# uDuino.net
KiCad netlist of a schematic drawn in EAGLE
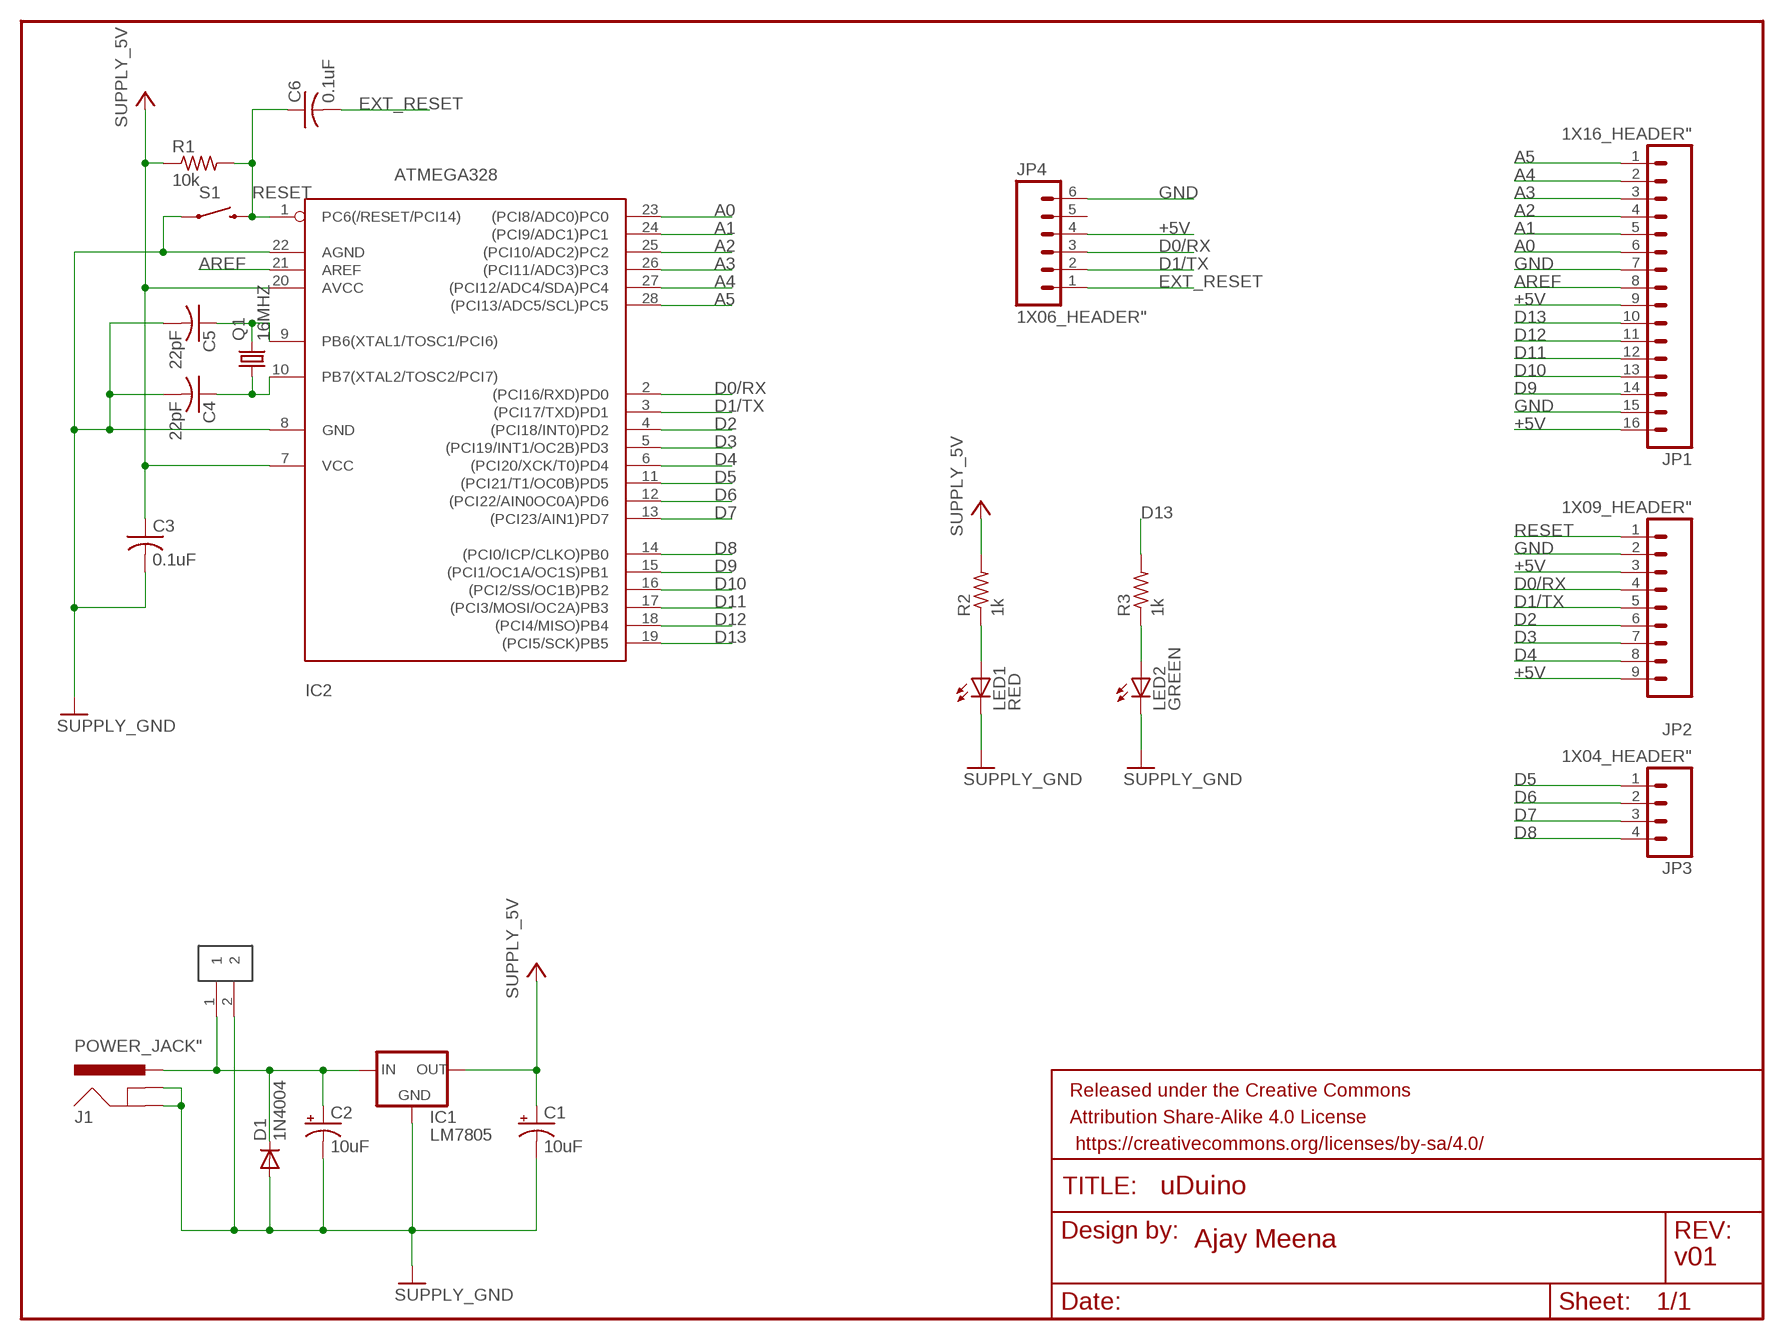
[diagram p0: schematic, sheet 1]

(export (version "E")
  (design (tool "Eeschema 10.0.6"))
  (components
    (comp (ref "C1")
      (value "10uF")
      (footprint "eagle-import:ELECTROLYTIC_CAP")
      (libsource (lib "eagle-import") (part "ELECTROLYTIC_CAP2.54MM"))
    )
    (comp (ref "C2")
      (value "10uF")
      (footprint "eagle-import:ELECTROLYTIC_CAP")
      (libsource (lib "eagle-import") (part "ELECTROLYTIC_CAP2.54MM"))
    )
    (comp (ref "C3")
      (value "0.1uF")
      (footprint "eagle-import:UNPOLARIZED_CAP")
      (libsource (lib "eagle-import") (part "UNPOLARIZED_CAP{dblquote}"))
    )
    (comp (ref "C4")
      (value "22pF")
      (footprint "eagle-import:UNPOLARIZED_CAP")
      (libsource (lib "eagle-import") (part "UNPOLARIZED_CAP{dblquote}"))
    )
    (comp (ref "C5")
      (value "22pF")
      (footprint "eagle-import:UNPOLARIZED_CAP")
      (libsource (lib "eagle-import") (part "UNPOLARIZED_CAP{dblquote}"))
    )
    (comp (ref "C6")
      (value "0.1uF")
      (footprint "eagle-import:UNPOLARIZED_CAP")
      (libsource (lib "eagle-import") (part "UNPOLARIZED_CAP{dblquote}"))
    )
    (comp (ref "D1")
      (value "1N4004")
      (footprint "eagle-import:DO41-10")
      (libsource (lib "eagle-import") (part "1N4004"))
    )
    (comp (ref "FRAME1")
      (value "FRAME-LETTERNO_PACKAGE")
      (footprint "eagle-import:DUMMY")
      (fields
        (field (name "DESIGNER") "Nobody")
        (field (name "VERSION") "v01")
        (field (name "DESIGNER_1") "Ajay Meena")
      )
      (libsource (lib "eagle-import") (part "FRAME-LETTERNO_PACKAGE"))
    )
    (comp (ref "IC1")
      (value "LM7805")
      (footprint "eagle-import:L4931_REGULATOR")
      (libsource (lib "eagle-import") (part "REGULATOR"))
    )
    (comp (ref "IC2")
      (value "ATMEGA328")
      (footprint "eagle-import:ATMEGA328")
      (libsource (lib "eagle-import") (part "ATMEGA328{dblquote}"))
    )
    (comp (ref "J1")
      (value "POWER_JACK\"")
      (footprint "eagle-import:POWER_JACK")
      (libsource (lib "eagle-import") (part "POWER_JACK{dblquote}"))
    )
    (comp (ref "JP1")
      (value "1X16_HEADER\"")
      (footprint "eagle-import:1X16_HEADER")
      (libsource (lib "eagle-import") (part "1X16_HEADER{dblquote}"))
    )
    (comp (ref "JP2")
      (value "1X09_HEADER\"")
      (footprint "eagle-import:1X09_HEADER")
      (libsource (lib "eagle-import") (part "1X09_HEADER{dblquote}"))
    )
    (comp (ref "JP3")
      (value "1X04_HEADER\"")
      (footprint "eagle-import:1X04_HEADER")
      (libsource (lib "eagle-import") (part "1X04_HEADER{dblquote}"))
    )
    (comp (ref "JP4")
      (value "1X06_HEADER\"")
      (footprint "eagle-import:1X06_HEADER")
      (libsource (lib "eagle-import") (part "1X06_HEADER{dblquote}"))
    )
    (comp (ref "JP5")
      (value "1X02_HEADER")
      (footprint "eagle-import:1X02_HEADER")
      (libsource (lib "eagle-import") (part "1X02_HEADER"))
    )
    (comp (ref "LED1")
      (value "RED")
      (footprint "eagle-import:LED5MM")
      (libsource (lib "eagle-import") (part "LED5MM"))
    )
    (comp (ref "LED2")
      (value "GREEN")
      (footprint "eagle-import:LED5MM")
      (libsource (lib "eagle-import") (part "LED5MM"))
    )
    (comp (ref "Q1")
      (value "16MHZ")
      (footprint "eagle-import:HC49_S")
      (libsource (lib "eagle-import") (part "CRYSTALHC49S"))
    )
    (comp (ref "R1")
      (value "10k")
      (footprint "eagle-import:0204_7")
      (libsource (lib "eagle-import") (part "R-US_0204/7"))
    )
    (comp (ref "R2")
      (value "1k")
      (footprint "eagle-import:0204_7")
      (libsource (lib "eagle-import") (part "R-US_0204/7"))
    )
    (comp (ref "R3")
      (value "1k")
      (footprint "eagle-import:0204_7")
      (libsource (lib "eagle-import") (part "R-US_0204/7"))
    )
    (comp (ref "S1")
      (value "MOMENTARY_SWITCH\"")
      (footprint "eagle-import:MOMENTARY_SWITCH")
      (libsource (lib "eagle-import") (part "MOMENTARY_SWITCH{dblquote}"))
    )
  )
  (nets
    (net (code "1") (name "/A0") (class "Default")
      (node (ref "IC2") (pin "23") (pinfunction "(PCI8/ADC0)PC0_23") (pintype "bidirectional"))
      (node (ref "JP1") (pin "6") (pinfunction "6_6") (pintype "passive"))
    )
    (net (code "2") (name "/A1") (class "Default")
      (node (ref "IC2") (pin "24") (pinfunction "(PCI9/ADC1)PC1_24") (pintype "bidirectional"))
      (node (ref "JP1") (pin "5") (pinfunction "5_5") (pintype "passive"))
    )
    (net (code "3") (name "/A2") (class "Default")
      (node (ref "IC2") (pin "25") (pinfunction "(PCI10/ADC2)PC2_25") (pintype "bidirectional"))
      (node (ref "JP1") (pin "4") (pinfunction "4_4") (pintype "passive"))
    )
    (net (code "4") (name "/A3") (class "Default")
      (node (ref "IC2") (pin "26") (pinfunction "(PCI11/ADC3)PC3_26") (pintype "bidirectional"))
      (node (ref "JP1") (pin "3") (pinfunction "3_3") (pintype "passive"))
    )
    (net (code "5") (name "/A4") (class "Default")
      (node (ref "IC2") (pin "27") (pinfunction "(PCI12/ADC4/SDA)PC4_27") (pintype "bidirectional"))
      (node (ref "JP1") (pin "2") (pinfunction "2_2") (pintype "passive"))
    )
    (net (code "6") (name "/A5") (class "Default")
      (node (ref "IC2") (pin "28") (pinfunction "(PCI13/ADC5/SCL)PC5_28") (pintype "bidirectional"))
      (node (ref "JP1") (pin "1") (pinfunction "1_1") (pintype "passive"))
    )
    (net (code "7") (name "/AREF") (class "Default")
      (node (ref "IC2") (pin "21") (pinfunction "AREF_21") (pintype "bidirectional"))
      (node (ref "JP1") (pin "8") (pinfunction "8_8") (pintype "passive"))
    )
    (net (code "8") (name "/D0{slash}RX") (class "Default")
      (node (ref "IC2") (pin "2") (pinfunction "(PCI16/RXD)PD0_2") (pintype "bidirectional"))
      (node (ref "JP2") (pin "4") (pinfunction "4_4") (pintype "passive"))
      (node (ref "JP4") (pin "3") (pinfunction "3_3") (pintype "passive"))
    )
    (net (code "9") (name "/D1{slash}TX") (class "Default")
      (node (ref "IC2") (pin "3") (pinfunction "(PCI17/TXD)PD1_3") (pintype "bidirectional"))
      (node (ref "JP2") (pin "5") (pinfunction "5_5") (pintype "passive"))
      (node (ref "JP4") (pin "2") (pinfunction "2_2") (pintype "passive"))
    )
    (net (code "10") (name "/D2") (class "Default")
      (node (ref "IC2") (pin "4") (pinfunction "(PCI18/INT0)PD2_4") (pintype "bidirectional"))
      (node (ref "JP2") (pin "6") (pinfunction "6_6") (pintype "passive"))
    )
    (net (code "11") (name "/D3") (class "Default")
      (node (ref "IC2") (pin "5") (pinfunction "(PCI19/INT1/OC2B)PD3_5") (pintype "bidirectional"))
      (node (ref "JP2") (pin "7") (pinfunction "7_7") (pintype "passive"))
    )
    (net (code "12") (name "/D4") (class "Default")
      (node (ref "IC2") (pin "6") (pinfunction "(PCI20/XCK/T0)PD4_6") (pintype "bidirectional"))
      (node (ref "JP2") (pin "8") (pinfunction "8_8") (pintype "passive"))
    )
    (net (code "13") (name "/D5") (class "Default")
      (node (ref "IC2") (pin "11") (pinfunction "(PCI21/T1/OC0B)PD5_11") (pintype "bidirectional"))
      (node (ref "JP3") (pin "1") (pinfunction "1_1") (pintype "passive"))
    )
    (net (code "14") (name "/D6") (class "Default")
      (node (ref "IC2") (pin "12") (pinfunction "(PCI22/AIN0OC0A)PD6_12") (pintype "bidirectional"))
      (node (ref "JP3") (pin "2") (pinfunction "2_2") (pintype "passive"))
    )
    (net (code "15") (name "/D7") (class "Default")
      (node (ref "IC2") (pin "13") (pinfunction "(PCI23/AIN1)PD7_13") (pintype "bidirectional"))
      (node (ref "JP3") (pin "3") (pinfunction "3_3") (pintype "passive"))
    )
    (net (code "16") (name "/D8") (class "Default")
      (node (ref "IC2") (pin "14") (pinfunction "(PCI0/ICP/CLKO)PB0_14") (pintype "bidirectional"))
      (node (ref "JP3") (pin "4") (pinfunction "4_4") (pintype "passive"))
    )
    (net (code "17") (name "/D9") (class "Default")
      (node (ref "IC2") (pin "15") (pinfunction "(PCI1/OC1A/OC1S)PB1_15") (pintype "bidirectional"))
      (node (ref "JP1") (pin "14") (pinfunction "14_14") (pintype "passive"))
    )
    (net (code "18") (name "/D10") (class "Default")
      (node (ref "IC2") (pin "16") (pinfunction "(PCI2/SS/OC1B)PB2_16") (pintype "bidirectional"))
      (node (ref "JP1") (pin "13") (pinfunction "13_13") (pintype "passive"))
    )
    (net (code "19") (name "/D11") (class "Default")
      (node (ref "IC2") (pin "17") (pinfunction "(PCI3/MOSI/OC2A)PB3_17") (pintype "bidirectional"))
      (node (ref "JP1") (pin "12") (pinfunction "12_12") (pintype "passive"))
    )
    (net (code "20") (name "/D12") (class "Default")
      (node (ref "IC2") (pin "18") (pinfunction "(PCI4/MISO)PB4_18") (pintype "bidirectional"))
      (node (ref "JP1") (pin "11") (pinfunction "11_11") (pintype "passive"))
    )
    (net (code "21") (name "/D13") (class "Default")
      (node (ref "IC2") (pin "19") (pinfunction "(PCI5/SCK)PB5_19") (pintype "bidirectional"))
      (node (ref "JP1") (pin "10") (pinfunction "10_10") (pintype "passive"))
      (node (ref "R3") (pin "2") (pinfunction "2_2") (pintype "passive"))
    )
    (net (code "22") (name "/EXT_RESET") (class "Default")
      (node (ref "C6") (pin "2") (pinfunction "2_2") (pintype "passive"))
      (node (ref "JP4") (pin "1") (pinfunction "1_1") (pintype "passive"))
    )
    (net (code "23") (name "/RESET") (class "Default")
      (node (ref "C6") (pin "1") (pinfunction "1_1") (pintype "passive"))
      (node (ref "IC2") (pin "1") (pinfunction "PC6(/RESET/PCI14)_1") (pintype "bidirectional"))
      (node (ref "JP2") (pin "1") (pinfunction "1_1") (pintype "passive"))
      (node (ref "R1") (pin "2") (pinfunction "2_2") (pintype "passive"))
      (node (ref "S1") (pin "3") (pinfunction "2_3") (pintype "passive"))
    )
    (net (code "24") (name "Net-(C2-Pad+)") (class "Default")
      (node (ref "C2") (pin "+") (pinfunction "+_+") (pintype "passive"))
      (node (ref "D1") (pin "C") (pinfunction "C_C") (pintype "passive"))
      (node (ref "IC1") (pin "IN") (pinfunction "IN_IN") (pintype "input"))
      (node (ref "J1") (pin "PWR") (pinfunction "PWR_PWR") (pintype "bidirectional"))
      (node (ref "JP5") (pin "1") (pinfunction "1_1") (pintype "bidirectional"))
    )
    (net (code "25") (name "Net-(IC2-PB6(XTAL1{slash}TOSC1{slash}PCI6))") (class "Default")
      (node (ref "C5") (pin "1") (pinfunction "1_1") (pintype "passive"))
      (node (ref "IC2") (pin "9") (pinfunction "PB6(XTAL1/TOSC1/PCI6)_9") (pintype "bidirectional"))
      (node (ref "Q1") (pin "2") (pinfunction "2_2") (pintype "passive"))
    )
    (net (code "26") (name "Net-(IC2-PB7(XTAL2{slash}TOSC2{slash}PCI7))") (class "Default")
      (node (ref "C4") (pin "1") (pinfunction "1_1") (pintype "passive"))
      (node (ref "IC2") (pin "10") (pinfunction "PB7(XTAL2/TOSC2/PCI7)_10") (pintype "bidirectional"))
      (node (ref "Q1") (pin "1") (pinfunction "1_1") (pintype "passive"))
    )
    (net (code "27") (name "Net-(LED1-PadA)") (class "Default")
      (node (ref "LED1") (pin "A") (pinfunction "A_A") (pintype "passive"))
      (node (ref "R2") (pin "1") (pinfunction "1_1") (pintype "passive"))
    )
    (net (code "28") (name "Net-(LED2-PadA)") (class "Default")
      (node (ref "LED2") (pin "A") (pinfunction "A_A") (pintype "passive"))
      (node (ref "R3") (pin "1") (pinfunction "1_1") (pintype "passive"))
    )
    (net (code "29") (name "SUPPLY_5V") (class "Default")
      (node (ref "C1") (pin "+") (pinfunction "+_+") (pintype "passive"))
      (node (ref "C3") (pin "1") (pinfunction "1_1") (pintype "passive"))
      (node (ref "IC1") (pin "OUT") (pinfunction "OUT_OUT") (pintype "passive"))
      (node (ref "IC2") (pin "20") (pinfunction "AVCC_20") (pintype "bidirectional"))
      (node (ref "IC2") (pin "7") (pinfunction "VCC_7") (pintype "bidirectional"))
      (node (ref "JP1") (pin "16") (pinfunction "16_16") (pintype "passive"))
      (node (ref "JP1") (pin "9") (pinfunction "9_9") (pintype "passive"))
      (node (ref "JP2") (pin "3") (pinfunction "3_3") (pintype "passive"))
      (node (ref "JP2") (pin "9") (pinfunction "9_9") (pintype "passive"))
      (node (ref "JP4") (pin "4") (pinfunction "4_4") (pintype "passive"))
      (node (ref "R1") (pin "1") (pinfunction "1_1") (pintype "passive"))
      (node (ref "R2") (pin "2") (pinfunction "2_2") (pintype "passive"))
    )
    (net (code "30") (name "SUPPLY_GND") (class "Default")
      (node (ref "C1") (pin "-") (pinfunction "-_-") (pintype "passive"))
      (node (ref "C2") (pin "-") (pinfunction "-_-") (pintype "passive"))
      (node (ref "C3") (pin "2") (pinfunction "2_2") (pintype "passive"))
      (node (ref "C4") (pin "2") (pinfunction "2_2") (pintype "passive"))
      (node (ref "C5") (pin "2") (pinfunction "2_2") (pintype "passive"))
      (node (ref "D1") (pin "A") (pinfunction "A_A") (pintype "passive"))
      (node (ref "IC1") (pin "GND") (pinfunction "GND_GND") (pintype "input"))
      (node (ref "IC2") (pin "22") (pinfunction "AGND_22") (pintype "bidirectional"))
      (node (ref "IC2") (pin "8") (pinfunction "GND_8") (pintype "bidirectional"))
      (node (ref "J1") (pin "GND") (pinfunction "GND_GND") (pintype "bidirectional"))
      (node (ref "J1") (pin "GNDBREAK") (pinfunction "GNDBREAK_GNDBREAK") (pintype "bidirectional"))
      (node (ref "JP1") (pin "15") (pinfunction "15_15") (pintype "passive"))
      (node (ref "JP1") (pin "7") (pinfunction "7_7") (pintype "passive"))
      (node (ref "JP2") (pin "2") (pinfunction "2_2") (pintype "passive"))
      (node (ref "JP4") (pin "6") (pinfunction "6_6") (pintype "passive"))
      (node (ref "JP5") (pin "2") (pinfunction "2_2") (pintype "bidirectional"))
      (node (ref "LED1") (pin "K") (pinfunction "C_K") (pintype "passive"))
      (node (ref "LED2") (pin "K") (pinfunction "C_K") (pintype "passive"))
      (node (ref "S1") (pin "1") (pinfunction "1_1") (pintype "passive"))
    )
    (net (code "31") (name "unconnected-(JP4-Pad5)") (class "Default")
      (node (ref "JP4") (pin "5") (pinfunction "5_5") (pintype "passive"))
    )
  )
)
